# H0BR5_Frontend.net
KiCad netlist of a schematic drawn in Altium Designer
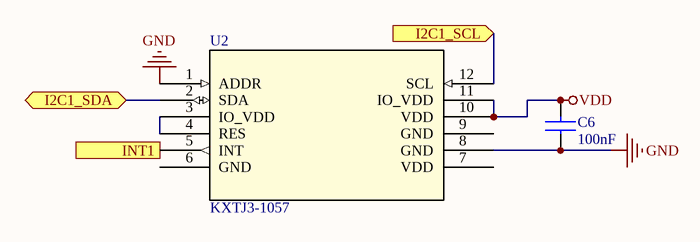
[diagram p0: H0BR5_Frontend.SchDoc]

(export (version "E")
  (design (tool "Eeschema 10.0.6"))
  (components
    (comp (ref "C6")
      (value "100nF")
      (footprint "C0603")
      (fields
        (field (name "MANUFACTURER") "Samsung Electro-Mechanics")
        (field (name "MANUFACTURER PART NUMBER") "CL10B104KA8NNNC")
        (field (name "TOLERANCE") "10%")
      )
      (libsource (lib "Hexabitz Altium Library") (part "generic Capacitor"))
    )
    (comp (ref "U2")
      (value "KXTJ3-1057")
      (footprint "LGA12_2X2X0.9_KNX")
      (description "No Description Available")
      (fields (field (name "COPYRIGHT") "Copyright (C) 2025 Ultra Librarian. All rights reserved."))
      (libsource (lib "KXTJ3-1057") (part "KXTJ3-1057"))
    )
  )
  (nets
    (net (code "1") (name "/I2C1_SCL") (class "Default")
      (node (ref "U2") (pin "12") (pinfunction "SCL_12") (pintype "input"))
    )
    (net (code "2") (name "/I2C1_SDA") (class "Default")
      (node (ref "U2") (pin "2") (pinfunction "SDA_2") (pintype "bidirectional"))
    )
    (net (code "3") (name "/INT1") (class "Default")
      (node (ref "U2") (pin "5") (pinfunction "INT_5") (pintype "output"))
    )
    (net (code "4") (name "GND") (class "Default")
      (node (ref "C6") (pin "1") (pinfunction "1_1") (pintype "passive"))
      (node (ref "U2") (pin "1") (pinfunction "ADDR_1") (pintype "input"))
      (node (ref "U2") (pin "8") (pinfunction "GND_8") (pintype "power_in"))
    )
    (net (code "5") (name "Net-(U2-RES)") (class "Default")
      (node (ref "U2") (pin "3") (pinfunction "IO_VDD_3") (pintype "power_in"))
      (node (ref "U2") (pin "4") (pinfunction "RES_4") (pintype "passive"))
    )
    (net (code "6") (name "VDD") (class "Default")
      (node (ref "C6") (pin "2") (pinfunction "2_2") (pintype "passive"))
      (node (ref "U2") (pin "10") (pinfunction "VDD_10") (pintype "power_in"))
      (node (ref "U2") (pin "11") (pinfunction "IO_VDD_11") (pintype "power_in"))
    )
    (net (code "7") (name "unconnected-(U2-GND-Pad6)") (class "Default")
      (node (ref "U2") (pin "6") (pinfunction "GND_6") (pintype "power_in"))
    )
    (net (code "8") (name "unconnected-(U2-GND-Pad9)") (class "Default")
      (node (ref "U2") (pin "9") (pinfunction "GND_9") (pintype "power_in"))
    )
    (net (code "9") (name "unconnected-(U2-VDD-Pad7)") (class "Default")
      (node (ref "U2") (pin "7") (pinfunction "VDD_7") (pintype "power_in"))
    )
  )
)
